# Power_1.net
KiCad netlist of a schematic drawn in Altium Designer
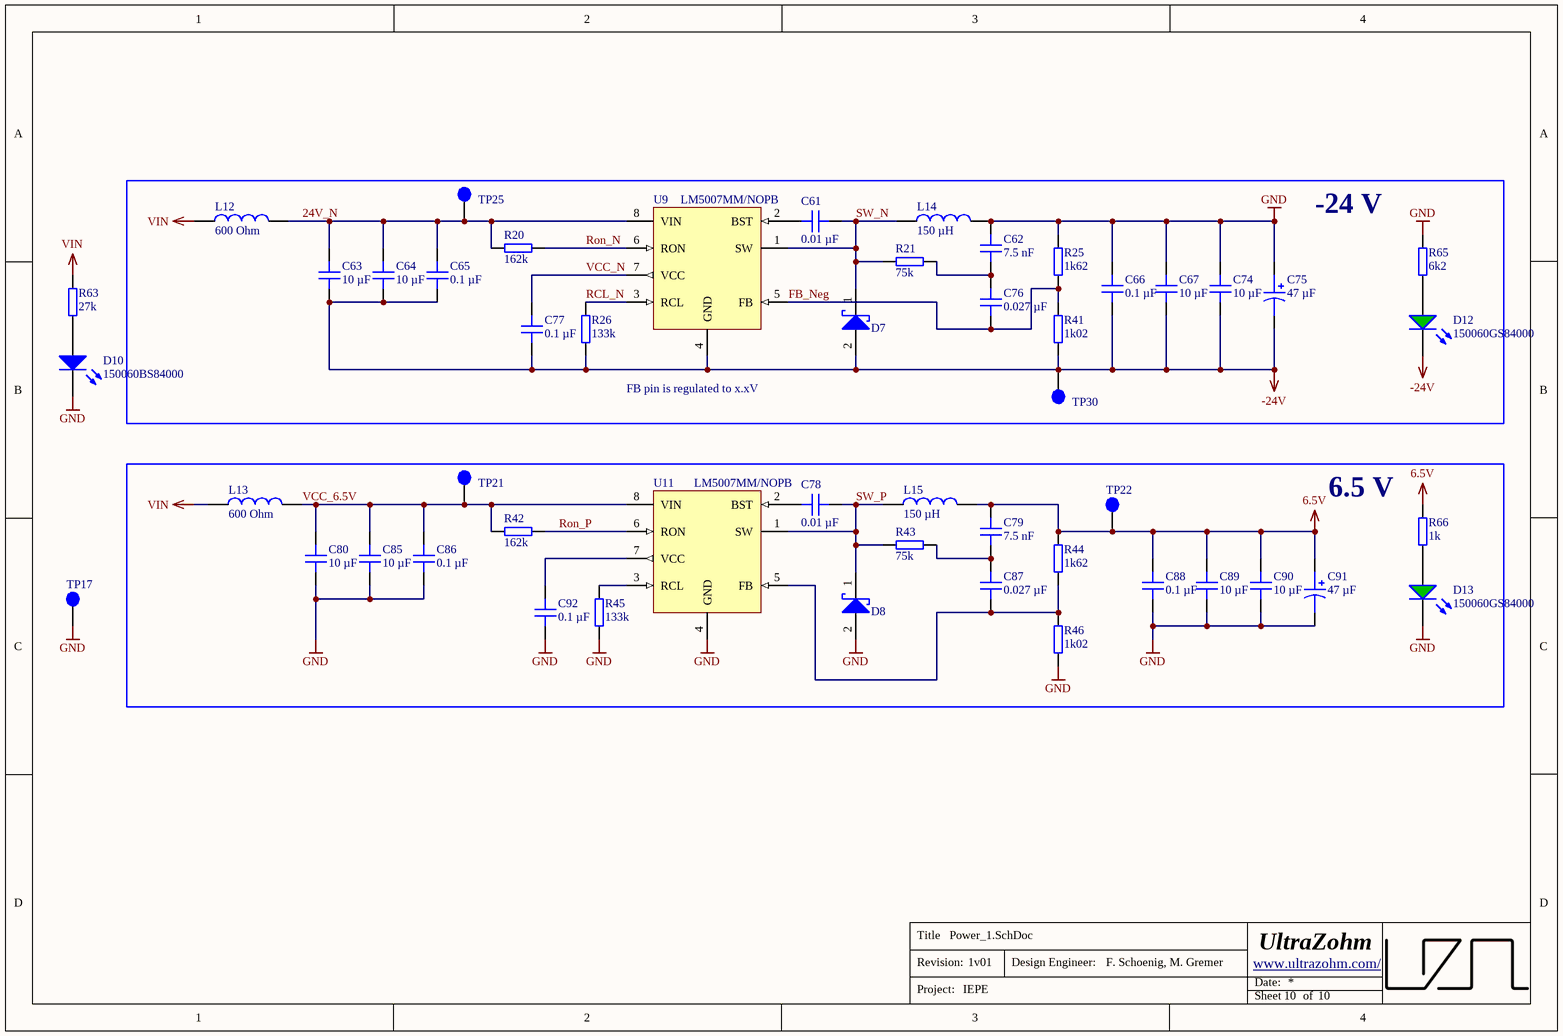
[diagram p0: Power_1.SchDoc]

(export (version "E")
  (design (tool "Eeschema 10.0.6"))
  (components
    (comp (ref "C61")
      (value "0.01 µF")
      (footprint "C_0603")
      (description "Capacitor 0603, 50 VDC, 0.01 µF, X7R")
      (fields
        (field (name "MANUFACTURER PART NUMBER") "GCJ188R71H103KA01D")
        (field (name "MANUFACTURER") "muRata")
        (field (name "CREATED FROM") "MGremer")
      )
      (libsource (lib "user") (part "Capacitor"))
    )
    (comp (ref "C62")
      (value "7.5 nF")
      (footprint "C_0603")
      (description "Capacitor 0603, 25 VDC, 7.5 nF, C0G")
      (fields
        (field (name "MANUFACTURER PART NUMBER") "C0603C752J3GACTU")
        (field (name "MANUFACTURER") "KEMET")
        (field (name "CREATED FROM") "MGremer")
      )
      (libsource (lib "user") (part "Capacitor"))
    )
    (comp (ref "C63")
      (value "10 µF")
      (footprint "C_1206")
      (description "Capacitor 1206, 35 VDC, 10 µF, X5R")
      (fields
        (field (name "MANUFACTURER PART NUMBER") "1206DD106MAT2A")
        (field (name "MANUFACTURER") "AVX")
        (field (name "CREATED FROM") "MGremer")
      )
      (libsource (lib "user") (part "Capacitor"))
    )
    (comp (ref "C64")
      (value "10 µF")
      (footprint "C_1206")
      (description "Capacitor 1206, 35 VDC, 10 µF, X5R")
      (fields
        (field (name "MANUFACTURER PART NUMBER") "1206DD106MAT2A")
        (field (name "MANUFACTURER") "AVX")
        (field (name "CREATED FROM") "MGremer")
      )
      (libsource (lib "user") (part "Capacitor"))
    )
    (comp (ref "C65")
      (value "0.1 µF")
      (footprint "C_0603")
      (description "Capacitor 0603, 50 VDC, 0.1 µF, X7R")
      (fields
        (field (name "MANUFACTURER PART NUMBER") "C0603X104K5RAC7411")
        (field (name "MANUFACTURER") "KEMET")
        (field (name "CREATED FROM") "MGremer")
      )
      (libsource (lib "user") (part "Capacitor"))
    )
    (comp (ref "C66")
      (value "0.1 µF")
      (footprint "C_0603")
      (description "Capacitor 0603, 50 VDC, 0.1 µF, X7R")
      (fields
        (field (name "MANUFACTURER PART NUMBER") "C0603X104K5RAC7411")
        (field (name "MANUFACTURER") "KEMET")
        (field (name "CREATED FROM") "MGremer")
      )
      (libsource (lib "user") (part "Capacitor"))
    )
    (comp (ref "C67")
      (value "10 µF")
      (footprint "C_1206")
      (description "Capacitor 1206, 35 VDC, 10 µF, X5R")
      (fields
        (field (name "MANUFACTURER PART NUMBER") "1206DD106MAT2A")
        (field (name "MANUFACTURER") "AVX")
        (field (name "CREATED FROM") "MGremer")
      )
      (libsource (lib "user") (part "Capacitor"))
    )
    (comp (ref "C74")
      (value "10 µF")
      (footprint "C_1206")
      (description "Capacitor 1206, 35 VDC, 10 µF, X5R")
      (fields
        (field (name "MANUFACTURER PART NUMBER") "1206DD106MAT2A")
        (field (name "MANUFACTURER") "AVX")
        (field (name "CREATED FROM") "MGremer")
      )
      (libsource (lib "user") (part "Capacitor"))
    )
    (comp (ref "C75")
      (value "47 µF")
      (footprint "CAPAE830X650N")
      (description "Capacitor, 47µF, 35VDC Al Electrolyt")
      (fields
        (field (name "MANUFACTURER PART NUMBER") "EEE-1VA470P")
        (field (name "MANUFACTURER") "Panasonic")
        (field (name "CREATED FROM") "T. Wendt")
      )
      (libsource (lib "user") (part "CAPACITOR_POLARIZED_EEE"))
    )
    (comp (ref "C76")
      (value "0.027 µF")
      (footprint "C_0603")
      (description "Capacitor 0603, 50 VDC, 27 nF, X7R")
      (fields
        (field (name "MANUFACTURER PART NUMBER") "06035C273J4T2A")
        (field (name "MANUFACTURER") "AVX")
        (field (name "CREATED FROM") "MGremer")
      )
      (libsource (lib "user") (part "Capacitor"))
    )
    (comp (ref "C77")
      (value "0.1 µF")
      (footprint "C_0603")
      (description "Capacitor 0603, 50 VDC, 0.1 µF, X7R")
      (fields
        (field (name "MANUFACTURER PART NUMBER") "C0603X104K5RAC7411")
        (field (name "MANUFACTURER") "KEMET")
        (field (name "CREATED FROM") "MGremer")
      )
      (libsource (lib "user") (part "Capacitor"))
    )
    (comp (ref "C78")
      (value "0.01 µF")
      (footprint "C_0603")
      (description "Capacitor 0603, 50 VDC, 0.01 µF, X7R")
      (fields
        (field (name "MANUFACTURER PART NUMBER") "GCJ188R71H103KA01D")
        (field (name "MANUFACTURER") "muRata")
        (field (name "CREATED FROM") "MGremer")
      )
      (libsource (lib "user") (part "Capacitor"))
    )
    (comp (ref "C79")
      (value "7.5 nF")
      (footprint "C_0603")
      (description "Capacitor 0603, 25 VDC, 7.5 nF, C0G")
      (fields
        (field (name "MANUFACTURER PART NUMBER") "C0603C752J3GACTU")
        (field (name "MANUFACTURER") "KEMET")
        (field (name "CREATED FROM") "MGremer")
      )
      (libsource (lib "user") (part "Capacitor"))
    )
    (comp (ref "C80")
      (value "10 µF")
      (footprint "C_1206")
      (description "Capacitor 1206, 35 VDC, 10 µF, X5R")
      (fields
        (field (name "MANUFACTURER PART NUMBER") "1206DD106MAT2A")
        (field (name "MANUFACTURER") "AVX")
        (field (name "CREATED FROM") "MGremer")
      )
      (libsource (lib "user") (part "Capacitor"))
    )
    (comp (ref "C85")
      (value "10 µF")
      (footprint "C_1206")
      (description "Capacitor 1206, 35 VDC, 10 µF, X5R")
      (fields
        (field (name "MANUFACTURER PART NUMBER") "1206DD106MAT2A")
        (field (name "MANUFACTURER") "AVX")
        (field (name "CREATED FROM") "MGremer")
      )
      (libsource (lib "user") (part "Capacitor"))
    )
    (comp (ref "C86")
      (value "0.1 µF")
      (footprint "C_0603")
      (description "Capacitor 0603, 50 VDC, 0.1 µF, X7R")
      (fields
        (field (name "MANUFACTURER PART NUMBER") "C0603X104K5RAC7411")
        (field (name "MANUFACTURER") "KEMET")
        (field (name "CREATED FROM") "MGremer")
      )
      (libsource (lib "user") (part "Capacitor"))
    )
    (comp (ref "C87")
      (value "0.027 µF")
      (footprint "C_0603")
      (description "Capacitor 0603, 50 VDC, 27 nF, X7R")
      (fields
        (field (name "MANUFACTURER PART NUMBER") "06035C273J4T2A")
        (field (name "MANUFACTURER") "AVX")
        (field (name "CREATED FROM") "MGremer")
      )
      (libsource (lib "user") (part "Capacitor"))
    )
    (comp (ref "C88")
      (value "0.1 µF")
      (footprint "C_0603")
      (description "Capacitor 0603, 50 VDC, 0.1 µF, X7R")
      (fields
        (field (name "MANUFACTURER PART NUMBER") "C0603X104K5RAC7411")
        (field (name "MANUFACTURER") "KEMET")
        (field (name "CREATED FROM") "MGremer")
      )
      (libsource (lib "user") (part "Capacitor"))
    )
    (comp (ref "C89")
      (value "10 µF")
      (footprint "C_1206")
      (description "Capacitor 1206, 35 VDC, 10 µF, X5R")
      (fields
        (field (name "MANUFACTURER PART NUMBER") "1206DD106MAT2A")
        (field (name "MANUFACTURER") "AVX")
        (field (name "CREATED FROM") "MGremer")
      )
      (libsource (lib "user") (part "Capacitor"))
    )
    (comp (ref "C90")
      (value "10 µF")
      (footprint "C_1206")
      (description "Capacitor 1206, 35 VDC, 10 µF, X5R")
      (fields
        (field (name "MANUFACTURER PART NUMBER") "1206DD106MAT2A")
        (field (name "MANUFACTURER") "AVX")
        (field (name "CREATED FROM") "MGremer")
      )
      (libsource (lib "user") (part "Capacitor"))
    )
    (comp (ref "C91")
      (value "47 µF")
      (footprint "CAPAE830X650N")
      (description "Capacitor, 47µF, 35VDC Al Electrolyt")
      (fields
        (field (name "MANUFACTURER PART NUMBER") "EEE-1VA470P")
        (field (name "MANUFACTURER") "Panasonic")
        (field (name "CREATED FROM") "T. Wendt")
      )
      (libsource (lib "user") (part "CAPACITOR_POLARIZED_EEE"))
    )
    (comp (ref "C92")
      (value "0.1 µF")
      (footprint "C_0603")
      (description "Capacitor 0603, 50 VDC, 0.1 µF, X7R")
      (fields
        (field (name "MANUFACTURER PART NUMBER") "C0603X104K5RAC7411")
        (field (name "MANUFACTURER") "KEMET")
        (field (name "CREATED FROM") "MGremer")
      )
      (libsource (lib "user") (part "Capacitor"))
    )
    (comp (ref "D7")
      (value "BYS12-90-E3/TR3")
      (footprint "DIOM4227X23N")
      (description "Schottky Rectifier, 1.5 A, 90 V")
      (fields
        (field (name "MANUFACTURER") "Vishay General Semiconductor")
        (field (name "CREATED FROM") "MGremer")
      )
      (libsource (lib "user") (part "STPS340-Y"))
    )
    (comp (ref "D8")
      (value "BYS12-90-E3/TR3")
      (footprint "DIOM4227X23N")
      (description "Schottky Rectifier, 1.5 A, 90 V")
      (fields
        (field (name "MANUFACTURER") "Vishay General Semiconductor")
        (field (name "CREATED FROM") "MGremer")
      )
      (libsource (lib "user") (part "STPS340-Y"))
    )
    (comp (ref "D10")
      (value "150060BS84000")
      (footprint "WL-SMCW_0603")
      (description "WL-SMCW SMD Mono-color Chip LED Waterclear Blue")
      (fields (field (name "MANUFACTURER") "Wuerth Elektronik") (field (name "CREATED FROM") "MGremer"))
      (libsource (lib "user") (part "LED_Blue"))
    )
    (comp (ref "D12")
      (value "150060GS84000")
      (footprint "WL-SMCW_0603")
      (description "WL-SMCW SMD Mono-color Chip LED Waterclear Green")
      (fields (field (name "MANUFACTURER") "Wuerth Elektronik") (field (name "CREATED FROM") "MGremer"))
      (libsource (lib "user") (part "LED_Green"))
    )
    (comp (ref "D13")
      (value "150060GS84000")
      (footprint "WL-SMCW_0603")
      (description "WL-SMCW SMD Mono-color Chip LED Waterclear Green")
      (fields (field (name "MANUFACTURER") "Wuerth Elektronik") (field (name "CREATED FROM") "MGremer"))
      (libsource (lib "user") (part "LED_Green"))
    )
    (comp (ref "L12")
      (value "600 Ohm")
      (footprint "WE-CBF_0805_High Current")
      (description "Inductance, 0805, 100 MHz, 600 Ohm, 2 A")
      (fields
        (field (name "MANUFACTURER PART NUMBER") "742792040")
        (field (name "MANUFACTURER") "Wurth Elektronik")
        (field (name "CREATED FROM") "MGremer")
      )
      (libsource (lib "user") (part "WE-CBF"))
    )
    (comp (ref "L13")
      (value "600 Ohm")
      (footprint "WE-CBF_0805_High Current")
      (description "Inductance, 0805, 100 MHz, 600 Ohm, 2 A")
      (fields
        (field (name "MANUFACTURER PART NUMBER") "742792040")
        (field (name "MANUFACTURER") "Wurth Elektronik")
        (field (name "CREATED FROM") "MGremer")
      )
      (libsource (lib "user") (part "WE-CBF"))
    )
    (comp (ref "L14")
      (value "150 µH")
      (footprint "SMT_inductor_1050")
      (description "Inductor SMT, 10 x 10, 150 µH, 0.8 A")
      (fields
        (field (name "MF") "EPCOS / TDK")
        (field (name "MPN") "B82464G4154M")
        (field (name "CREATED FROM") "MGremer")
      )
      (libsource (lib "user") (part "B82464G4154M"))
    )
    (comp (ref "L15")
      (value "150 µH")
      (footprint "SMT_inductor_1050")
      (description "Inductor SMT, 10 x 10, 150 µH, 0.8 A")
      (fields
        (field (name "MF") "EPCOS / TDK")
        (field (name "MPN") "B82464G4154M")
        (field (name "CREATED FROM") "MGremer")
      )
      (libsource (lib "user") (part "B82464G4154M"))
    )
    (comp (ref "R20")
      (value "162k")
      (footprint "RES 0603_1608")
      (description "SMD resistor 1%")
      (fields
        (field (name "MANUFACTURER PART NUMBER") "CR0603-FX-1623ELF")
        (field (name "MANUFACTURER") "Burns")
        (field (name "CREATED FROM") "MGremer")
      )
      (libsource (lib "user") (part "Resistor"))
    )
    (comp (ref "R21")
      (value "75k")
      (footprint "RES 0603_1608")
      (description "SMD resistor E24 series")
      (fields
        (field (name "MANUFACTURER PART NUMBER") "RK73B1JTTD753J")
        (field (name "MANUFACTURER") "KOA Speer")
        (field (name "CREATED FROM") "MGremer")
      )
      (libsource (lib "user") (part "Resistor"))
    )
    (comp (ref "R25")
      (value "1k62")
      (footprint "RES 0603_1608")
      (description "SMD resistor 1%")
      (fields
        (field (name "MANUFACTURER PART NUMBER") "ERJ-P03F1621V")
        (field (name "MANUFACTURER") "Panasonic")
        (field (name "CREATED FROM") "MGremer")
      )
      (libsource (lib "user") (part "Resistor"))
    )
    (comp (ref "R26")
      (value "133k")
      (footprint "RES 0603_1608")
      (description "SMD resistor 1%")
      (fields
        (field (name "MANUFACTURER PART NUMBER") "CR0603-FX-1333ELF")
        (field (name "MANUFACTURER") "Burns")
        (field (name "CREATED FROM") "MGremer")
      )
      (libsource (lib "user") (part "Resistor"))
    )
    (comp (ref "R41")
      (value "1k02")
      (footprint "RES 0603_1608")
      (description "SMD resistor 1%")
      (fields
        (field (name "MANUFACTURER PART NUMBER") "CR0603-FX-1021ELF")
        (field (name "MANUFACTURER") "Burns")
        (field (name "CREATED FROM") "MGremer")
      )
      (libsource (lib "user") (part "Resistor"))
    )
    (comp (ref "R42")
      (value "162k")
      (footprint "RES 0603_1608")
      (description "SMD resistor 1%")
      (fields
        (field (name "MANUFACTURER PART NUMBER") "CR0603-FX-1623ELF")
        (field (name "MANUFACTURER") "Burns")
        (field (name "CREATED FROM") "MGremer")
      )
      (libsource (lib "user") (part "Resistor"))
    )
    (comp (ref "R43")
      (value "75k")
      (footprint "RES 0603_1608")
      (description "SMD resistor E24 series")
      (fields
        (field (name "MANUFACTURER PART NUMBER") "RK73B1JTTD753J")
        (field (name "MANUFACTURER") "KOA Speer")
        (field (name "CREATED FROM") "MGremer")
      )
      (libsource (lib "user") (part "Resistor"))
    )
    (comp (ref "R44")
      (value "1k62")
      (footprint "RES 0603_1608")
      (description "SMD resistor 1%")
      (fields
        (field (name "MANUFACTURER PART NUMBER") "ERJ-P03F1621V")
        (field (name "MANUFACTURER") "Panasonic")
        (field (name "CREATED FROM") "MGremer")
      )
      (libsource (lib "user") (part "Resistor"))
    )
    (comp (ref "R45")
      (value "133k")
      (footprint "RES 0603_1608")
      (description "SMD resistor 1%")
      (fields
        (field (name "MANUFACTURER PART NUMBER") "CR0603-FX-1333ELF")
        (field (name "MANUFACTURER") "Burns")
        (field (name "CREATED FROM") "MGremer")
      )
      (libsource (lib "user") (part "Resistor"))
    )
    (comp (ref "R46")
      (value "1k02")
      (footprint "RES 0603_1608")
      (description "SMD resistor 1%")
      (fields
        (field (name "MANUFACTURER PART NUMBER") "CR0603-FX-1021ELF")
        (field (name "MANUFACTURER") "Burns")
        (field (name "CREATED FROM") "MGremer")
      )
      (libsource (lib "user") (part "Resistor"))
    )
    (comp (ref "R63")
      (value "27k")
      (footprint "RES 0603_1608")
      (description "SMD resistor E24 series")
      (fields
        (field (name "MANUFACTURER PART NUMBER") "RK73B1JTTD273J")
        (field (name "MANUFACTURER") "KOA Speer")
        (field (name "CREATED FROM") "MGremer")
      )
      (libsource (lib "user") (part "Resistor"))
    )
    (comp (ref "R65")
      (value "6k2")
      (footprint "RES 0603_1608")
      (description "SMD resistor E24 series")
      (fields
        (field (name "MANUFACTURER PART NUMBER") "RK73B1JTTD622J")
        (field (name "MANUFACTURER") "KOA Speer")
        (field (name "CREATED FROM") "MGremer")
      )
      (libsource (lib "user") (part "Resistor"))
    )
    (comp (ref "R66")
      (value "1k")
      (footprint "RES 0603_1608")
      (description "SMD resistor E24 series")
      (fields
        (field (name "MANUFACTURER PART NUMBER") "RK73B1JTTDD102J")
        (field (name "MANUFACTURER") "KOA Speer")
        (field (name "CREATED FROM") "MGremer")
      )
      (libsource (lib "user") (part "Resistor"))
    )
    (comp (ref "TP17")
      (value "-")
      (footprint "TP_1mm")
      (description "Test Point 1 mm")
      (fields (field (name "CREATED") "2018_06_25_AGeiger") (field (name "CREATED FROM") "MGremer"))
      (libsource (lib "user") (part "TP_1mm"))
    )
    (comp (ref "TP21")
      (value "-")
      (footprint "TP_1mm")
      (description "Test Point 1 mm")
      (fields (field (name "CREATED") "2018_06_25_AGeiger") (field (name "CREATED FROM") "MGremer"))
      (libsource (lib "user") (part "TP_1mm"))
    )
    (comp (ref "TP22")
      (value "-")
      (footprint "TP_1mm")
      (description "Test Point 1 mm")
      (fields (field (name "CREATED") "2018_06_25_AGeiger") (field (name "CREATED FROM") "MGremer"))
      (libsource (lib "user") (part "TP_1mm"))
    )
    (comp (ref "TP25")
      (value "-")
      (footprint "TP_1mm")
      (description "Test Point 1 mm")
      (fields (field (name "CREATED") "2018_06_25_AGeiger") (field (name "CREATED FROM") "MGremer"))
      (libsource (lib "user") (part "TP_1mm"))
    )
    (comp (ref "TP30")
      (value "-")
      (footprint "TP_1mm")
      (description "Test Point 1 mm")
      (fields (field (name "CREATED") "2018_06_25_AGeiger") (field (name "CREATED FROM") "MGremer"))
      (libsource (lib "user") (part "TP_1mm"))
    )
    (comp (ref "U9")
      (value "LM5007MM/NOPB")
      (footprint "TSOP65P490X110-8N")
      (fields (field (name "MANUFACTURER") "Texas Instruments") (field (name "CREATED FROM") "MGremer"))
      (libsource (lib "user") (part "LM5007"))
    )
    (comp (ref "U11")
      (value "LM5007MM/NOPB")
      (footprint "TSOP65P490X110-8N")
      (fields (field (name "MANUFACTURER") "Texas Instruments") (field (name "CREATED FROM") "MGremer"))
      (libsource (lib "user") (part "LM5007"))
    )
  )
  (nets
    (net (code "1") (name "-24V") (class "Default")
      (node (ref "C63") (pin "1") (pinfunction "1_1") (pintype "passive"))
      (node (ref "C64") (pin "1") (pinfunction "1_1") (pintype "passive"))
      (node (ref "C65") (pin "1") (pinfunction "1_1") (pintype "passive"))
      (node (ref "C66") (pin "1") (pinfunction "1_1") (pintype "passive"))
      (node (ref "C67") (pin "1") (pinfunction "1_1") (pintype "passive"))
      (node (ref "C74") (pin "1") (pinfunction "1_1") (pintype "passive"))
      (node (ref "C75") (pin "2") (pinfunction "2_2") (pintype "passive"))
      (node (ref "C77") (pin "1") (pinfunction "1_1") (pintype "passive"))
      (node (ref "D12") (pin "1") (pinfunction "K_1") (pintype "passive"))
      (node (ref "D7") (pin "2") (pinfunction "A_2") (pintype "passive"))
      (node (ref "R26") (pin "1") (pinfunction "1_1") (pintype "passive"))
      (node (ref "R41") (pin "1") (pinfunction "1_1") (pintype "passive"))
      (node (ref "TP30") (pin "1") (pintype "passive"))
      (node (ref "U9") (pin "4") (pinfunction "GND_4") (pintype "power_in"))
    )
    (net (code "2") (name "/24V_N") (class "Default")
      (node (ref "C63") (pin "2") (pinfunction "2_2") (pintype "passive"))
      (node (ref "C64") (pin "2") (pinfunction "2_2") (pintype "passive"))
      (node (ref "C65") (pin "2") (pinfunction "2_2") (pintype "passive"))
      (node (ref "L12") (pin "2") (pinfunction "2_2") (pintype "passive"))
      (node (ref "R20") (pin "1") (pinfunction "1_1") (pintype "passive"))
      (node (ref "TP25") (pin "1") (pintype "passive"))
      (node (ref "U9") (pin "8") (pinfunction "VIN_8") (pintype "power_in"))
    )
    (net (code "3") (name "/FB_Neg") (class "Default")
      (node (ref "C76") (pin "1") (pinfunction "1_1") (pintype "passive"))
      (node (ref "R25") (pin "1") (pinfunction "1_1") (pintype "passive"))
      (node (ref "R41") (pin "2") (pinfunction "2_2") (pintype "passive"))
      (node (ref "U9") (pin "5") (pinfunction "FB_5") (pintype "input"))
    )
    (net (code "4") (name "/RCL_N") (class "Default")
      (node (ref "R26") (pin "2") (pinfunction "2_2") (pintype "passive"))
      (node (ref "U9") (pin "3") (pinfunction "RCL_3") (pintype "input"))
    )
    (net (code "5") (name "/Ron_N") (class "Default")
      (node (ref "R20") (pin "2") (pinfunction "2_2") (pintype "passive"))
      (node (ref "U9") (pin "6") (pinfunction "RON_6") (pintype "input"))
    )
    (net (code "6") (name "/Ron_P") (class "Default")
      (node (ref "R42") (pin "2") (pinfunction "2_2") (pintype "passive"))
      (node (ref "U11") (pin "6") (pinfunction "RON_6") (pintype "input"))
    )
    (net (code "7") (name "/SW_N") (class "Default")
      (node (ref "C61") (pin "2") (pinfunction "2_2") (pintype "passive"))
      (node (ref "D7") (pin "1") (pinfunction "K_1") (pintype "passive"))
      (node (ref "L14") (pin "1") (pinfunction "1_1") (pintype "passive"))
      (node (ref "R21") (pin "1") (pinfunction "1_1") (pintype "passive"))
      (node (ref "U9") (pin "1") (pinfunction "SW_1") (pintype "power_in"))
    )
    (net (code "8") (name "/SW_P") (class "Default")
      (node (ref "C78") (pin "2") (pinfunction "2_2") (pintype "passive"))
      (node (ref "D8") (pin "1") (pinfunction "K_1") (pintype "passive"))
      (node (ref "L15") (pin "1") (pinfunction "1_1") (pintype "passive"))
      (node (ref "R43") (pin "1") (pinfunction "1_1") (pintype "passive"))
      (node (ref "U11") (pin "1") (pinfunction "SW_1") (pintype "power_in"))
    )
    (net (code "9") (name "/VCC_6.5V") (class "Default")
      (node (ref "C80") (pin "2") (pinfunction "2_2") (pintype "passive"))
      (node (ref "C85") (pin "2") (pinfunction "2_2") (pintype "passive"))
      (node (ref "C86") (pin "2") (pinfunction "2_2") (pintype "passive"))
      (node (ref "L13") (pin "2") (pinfunction "2_2") (pintype "passive"))
      (node (ref "R42") (pin "1") (pinfunction "1_1") (pintype "passive"))
      (node (ref "TP21") (pin "1") (pintype "passive"))
      (node (ref "U11") (pin "8") (pinfunction "VIN_8") (pintype "power_in"))
    )
    (net (code "10") (name "/VCC_N") (class "Default")
      (node (ref "C77") (pin "2") (pinfunction "2_2") (pintype "passive"))
      (node (ref "U9") (pin "7") (pinfunction "VCC_7") (pintype "output"))
    )
    (net (code "11") (name "6.5V") (class "Default")
      (node (ref "C79") (pin "2") (pinfunction "2_2") (pintype "passive"))
      (node (ref "C88") (pin "2") (pinfunction "2_2") (pintype "passive"))
      (node (ref "C89") (pin "2") (pinfunction "2_2") (pintype "passive"))
      (node (ref "C90") (pin "2") (pinfunction "2_2") (pintype "passive"))
      (node (ref "C91") (pin "1") (pinfunction "1_1") (pintype "passive"))
      (node (ref "L15") (pin "2") (pinfunction "2_2") (pintype "passive"))
      (node (ref "R44") (pin "2") (pinfunction "2_2") (pintype "passive"))
      (node (ref "R66") (pin "2") (pinfunction "2_2") (pintype "passive"))
      (node (ref "TP22") (pin "1") (pintype "passive"))
    )
    (net (code "12") (name "GND") (class "Default")
      (node (ref "C62") (pin "2") (pinfunction "2_2") (pintype "passive"))
      (node (ref "C66") (pin "2") (pinfunction "2_2") (pintype "passive"))
      (node (ref "C67") (pin "2") (pinfunction "2_2") (pintype "passive"))
      (node (ref "C74") (pin "2") (pinfunction "2_2") (pintype "passive"))
      (node (ref "C75") (pin "1") (pinfunction "1_1") (pintype "passive"))
      (node (ref "C80") (pin "1") (pinfunction "1_1") (pintype "passive"))
      (node (ref "C85") (pin "1") (pinfunction "1_1") (pintype "passive"))
      (node (ref "C86") (pin "1") (pinfunction "1_1") (pintype "passive"))
      (node (ref "C88") (pin "1") (pinfunction "1_1") (pintype "passive"))
      (node (ref "C89") (pin "1") (pinfunction "1_1") (pintype "passive"))
      (node (ref "C90") (pin "1") (pinfunction "1_1") (pintype "passive"))
      (node (ref "C91") (pin "2") (pinfunction "2_2") (pintype "passive"))
      (node (ref "C92") (pin "1") (pinfunction "1_1") (pintype "passive"))
      (node (ref "D10") (pin "1") (pinfunction "K_1") (pintype "passive"))
      (node (ref "D13") (pin "1") (pinfunction "K_1") (pintype "passive"))
      (node (ref "D8") (pin "2") (pinfunction "A_2") (pintype "passive"))
      (node (ref "L14") (pin "2") (pinfunction "2_2") (pintype "passive"))
      (node (ref "R25") (pin "2") (pinfunction "2_2") (pintype "passive"))
      (node (ref "R45") (pin "1") (pinfunction "1_1") (pintype "passive"))
      (node (ref "R46") (pin "1") (pinfunction "1_1") (pintype "passive"))
      (node (ref "R65") (pin "2") (pinfunction "2_2") (pintype "passive"))
      (node (ref "TP17") (pin "1") (pintype "passive"))
      (node (ref "U11") (pin "4") (pinfunction "GND_4") (pintype "power_in"))
    )
    (net (code "13") (name "Net-(C62-Pad1)") (class "Default")
      (node (ref "C62") (pin "1") (pinfunction "1_1") (pintype "passive"))
      (node (ref "C76") (pin "2") (pinfunction "2_2") (pintype "passive"))
      (node (ref "R21") (pin "2") (pinfunction "2_2") (pintype "passive"))
    )
    (net (code "14") (name "Net-(C79-Pad1)") (class "Default")
      (node (ref "C79") (pin "1") (pinfunction "1_1") (pintype "passive"))
      (node (ref "C87") (pin "2") (pinfunction "2_2") (pintype "passive"))
      (node (ref "R43") (pin "2") (pinfunction "2_2") (pintype "passive"))
    )
    (net (code "15") (name "Net-(D10-A)") (class "Default")
      (node (ref "D10") (pin "2") (pinfunction "A_2") (pintype "passive"))
      (node (ref "R63") (pin "1") (pinfunction "1_1") (pintype "passive"))
    )
    (net (code "16") (name "Net-(D12-A)") (class "Default")
      (node (ref "D12") (pin "2") (pinfunction "A_2") (pintype "passive"))
      (node (ref "R65") (pin "1") (pinfunction "1_1") (pintype "passive"))
    )
    (net (code "17") (name "Net-(D13-A)") (class "Default")
      (node (ref "D13") (pin "2") (pinfunction "A_2") (pintype "passive"))
      (node (ref "R66") (pin "1") (pinfunction "1_1") (pintype "passive"))
    )
    (net (code "18") (name "Net-(U9-BST)") (class "Default")
      (node (ref "C61") (pin "1") (pinfunction "1_1") (pintype "passive"))
      (node (ref "U9") (pin "2") (pinfunction "BST_2") (pintype "input"))
    )
    (net (code "19") (name "Net-(U11-BST)") (class "Default")
      (node (ref "C78") (pin "1") (pinfunction "1_1") (pintype "passive"))
      (node (ref "U11") (pin "2") (pinfunction "BST_2") (pintype "input"))
    )
    (net (code "20") (name "Net-(U11-FB)") (class "Default")
      (node (ref "C87") (pin "1") (pinfunction "1_1") (pintype "passive"))
      (node (ref "R44") (pin "1") (pinfunction "1_1") (pintype "passive"))
      (node (ref "R46") (pin "2") (pinfunction "2_2") (pintype "passive"))
      (node (ref "U11") (pin "5") (pinfunction "FB_5") (pintype "input"))
    )
    (net (code "21") (name "Net-(U11-RCL)") (class "Default")
      (node (ref "R45") (pin "2") (pinfunction "2_2") (pintype "passive"))
      (node (ref "U11") (pin "3") (pinfunction "RCL_3") (pintype "input"))
    )
    (net (code "22") (name "Net-(U11-VCC)") (class "Default")
      (node (ref "C92") (pin "2") (pinfunction "2_2") (pintype "passive"))
      (node (ref "U11") (pin "7") (pinfunction "VCC_7") (pintype "output"))
    )
    (net (code "23") (name "VIN") (class "Default")
      (node (ref "L12") (pin "1") (pinfunction "1_1") (pintype "passive"))
      (node (ref "L13") (pin "1") (pinfunction "1_1") (pintype "passive"))
      (node (ref "R63") (pin "2") (pinfunction "2_2") (pintype "passive"))
    )
  )
)
